# fmu-io.net
KiCad netlist of a schematic drawn in Altium Designer
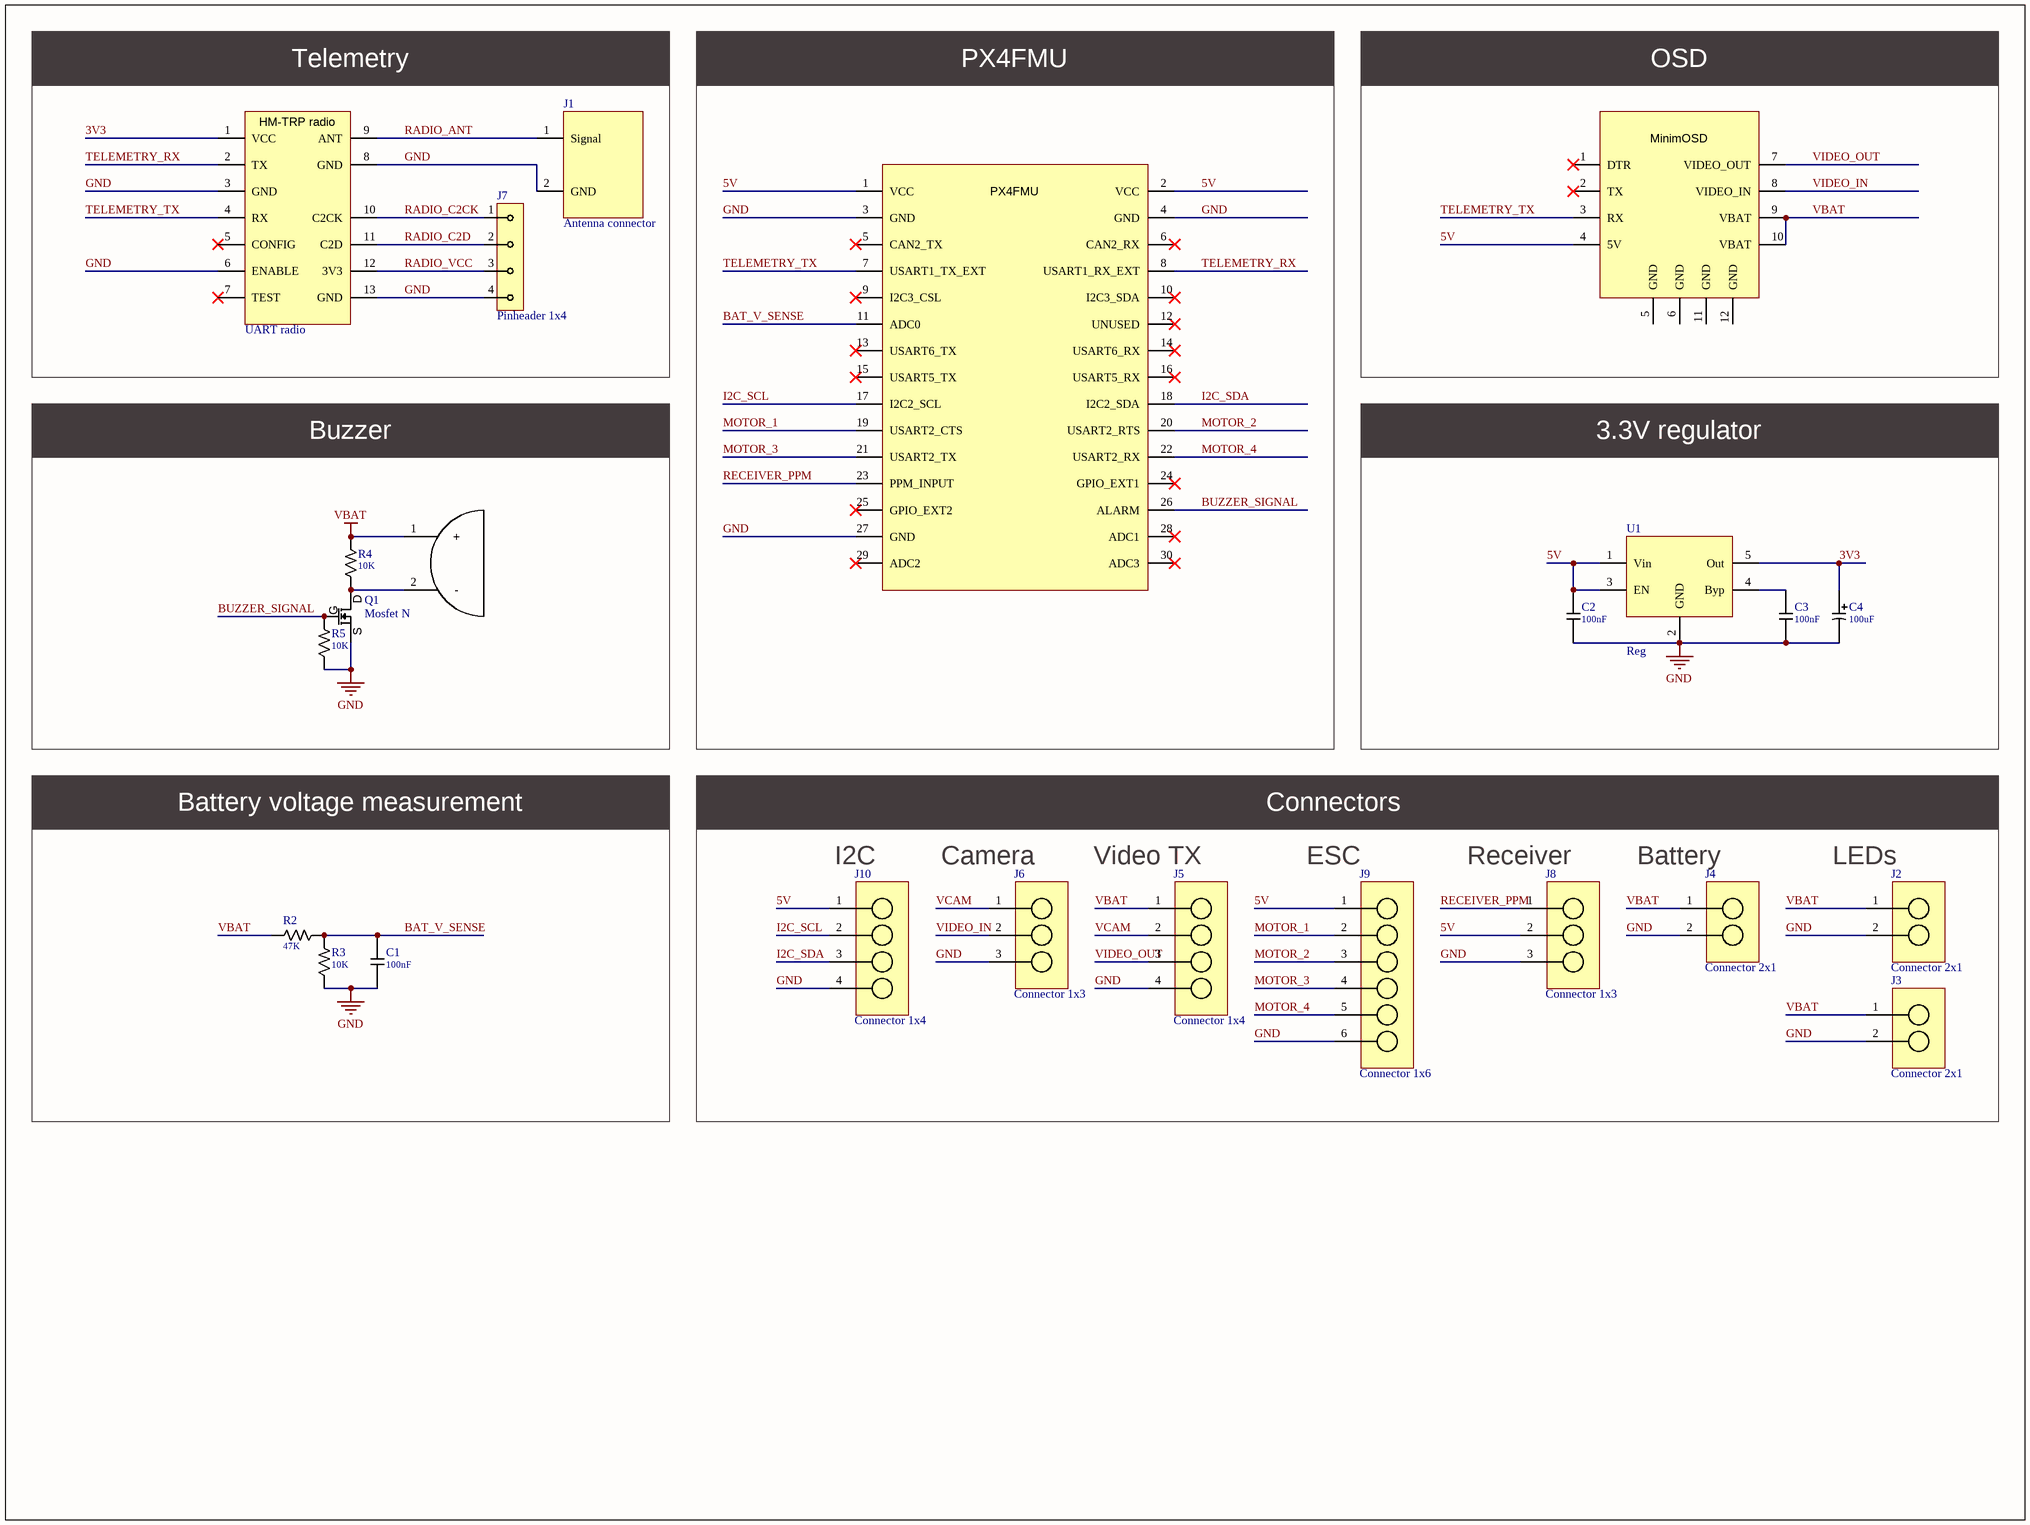
[diagram p0: fmu-io.SchDoc]

(export (version "E")
  (design (tool "Eeschema 10.0.6"))
  (components
    (comp (ref "C1")
      (value "100nF")
      (footprint "CAP-0603-GEN")
      (description "Capacitor")
      (fields (field (name "Comment") "CAPACITOR"))
      (libsource (lib "schematic-library") (part "CAPACITOR"))
    )
    (comp (ref "C2")
      (value "100nF")
      (footprint "CAP-0603-GEN")
      (description "Capacitor")
      (fields (field (name "Comment") "CAPACITOR"))
      (libsource (lib "custom") (part "CAPACITOR"))
    )
    (comp (ref "C3")
      (value "100nF")
      (footprint "CAP-0603-GEN")
      (description "Capacitor")
      (fields (field (name "Comment") "CAPACITOR"))
      (libsource (lib "custom") (part "CAPACITOR"))
    )
    (comp (ref "C4")
      (value "100uF")
      (footprint "CAP-1206-POL")
      (description "Polarized capacitor")
      (fields (field (name "Comment") "CAPACITOR-POLARIZED"))
      (libsource (lib "custom") (part "CAPACITOR-POLARIZED"))
    )
    (comp (ref "J1")
      (value "Antenna connector")
      (footprint "ANTENNA-CONNECTOR")
      (libsource (lib "schematic-library") (part "ANTENNA-CONNECTOR"))
    )
    (comp (ref "J2")
      (value "Connector 2x1")
      (footprint "DF13-2H-SMD")
      (description "Single row two contact connector")
      (libsource (lib "schematic-library") (part "CONNECTOR-1x2"))
    )
    (comp (ref "J3")
      (value "Connector 2x1")
      (footprint "DF13-2H-SMD")
      (description "Single row two contact connector")
      (libsource (lib "schematic-library") (part "CONNECTOR-1x2"))
    )
    (comp (ref "J4")
      (value "Connector 2x1")
      (footprint "JST-PA-2H-SMD")
      (description "Single row two contact connector")
      (libsource (lib "schematic-library") (part "CONNECTOR-1x2"))
    )
    (comp (ref "J5")
      (value "Connector 1x4")
      (footprint "DF13-4H-SMD")
      (description "Single row 4 contact connector")
      (libsource (lib "schematic-library") (part "CONNECTOR-1x4"))
    )
    (comp (ref "J6")
      (value "Connector 1x3")
      (footprint "DF13-3H-SMD")
      (description "Single row 3 contact connector")
      (libsource (lib "schematic-library") (part "CONNECTOR-1x3"))
    )
    (comp (ref "J7")
      (value "Pinheader 1x4")
      (footprint "PINHEADER-1x4-right-angle")
      (description "Single row four pin header")
      (libsource (lib "schematic-library") (part "PINHEADER-1x4"))
    )
    (comp (ref "J8")
      (value "Connector 1x3")
      (footprint "DF13-3H-SMD")
      (description "Single row 3 contact connector")
      (libsource (lib "schematic-library") (part "CONNECTOR-1x3"))
    )
    (comp (ref "J9")
      (value "Connector 1x6")
      (footprint "DF13-6H-SMD")
      (description "Single row 6 contact connector")
      (libsource (lib "schematic-library") (part "CONNECTOR-1x6"))
    )
    (comp (ref "J10")
      (value "Connector 1x4")
      (footprint "DF13-4H-SMD")
      (description "Single row 4 contact connector")
      (libsource (lib "schematic-library") (part "CONNECTOR-1x4"))
    )
    (comp (ref "OSD")
      (value "OSD")
      (footprint "MINIMOSD")
      (description "On-screen display")
      (libsource (lib "schematic-library") (part "MINIMOSD"))
    )
    (comp (ref "PX4FMU")
      (value "PX4FMU")
      (footprint "HEADER-2x15-SMD")
      (description "PX4FMU flight controller")
      (libsource (lib "schematic-library") (part "PX4FMU"))
    )
    (comp (ref "Q1")
      (value "Mosfet N")
      (footprint "SOT23-3")
      (description "N-channel mosfet")
      (libsource (lib "schematic-library") (part "MOSFET-N"))
    )
    (comp (ref "R1")
      (value "UART radio")
      (footprint "HM-TRP")
      (description "UART long range radio")
      (libsource (lib "schematic-library") (part "HM-TRP"))
    )
    (comp (ref "R2")
      (value "47K")
      (footprint "RESISTOR-0603")
      (description "Resistor")
      (fields (field (name "Comment") "RESISTOR"))
      (libsource (lib "schematic-library") (part "RESISTOR"))
    )
    (comp (ref "R3")
      (value "10K")
      (footprint "RESISTOR-0603")
      (description "Resistor")
      (fields (field (name "Comment") "RESISTOR"))
      (libsource (lib "schematic-library") (part "RESISTOR"))
    )
    (comp (ref "R4")
      (value "10K")
      (footprint "RESISTOR-0603")
      (description "Resistor")
      (fields (field (name "Comment") "RESISTOR"))
      (libsource (lib "schematic-library") (part "RESISTOR"))
    )
    (comp (ref "R5")
      (value "10K")
      (footprint "RESISTOR-0603")
      (description "Resistor")
      (fields (field (name "Comment") "RESISTOR"))
      (libsource (lib "schematic-library") (part "RESISTOR"))
    )
    (comp (ref "SG1")
      (value "Buzzer")
      (footprint "BUZZER-ABI-017-RC")
      (libsource (lib "schematic-library") (part "BUZZER"))
    )
    (comp (ref "U1")
      (value "Reg")
      (footprint "SOT23-5")
      (description "Voltage regulator")
      (libsource (lib "custom") (part "SOT23-REG"))
    )
  )
  (nets
    (net (code "1") (name "/3V3") (class "Default")
      (node (ref "C4") (pin "1") (pinfunction "1_1") (pintype "passive"))
      (node (ref "R1") (pin "1") (pinfunction "VCC_1") (pintype "passive"))
      (node (ref "U1") (pin "5") (pinfunction "Out_5") (pintype "passive"))
    )
    (net (code "2") (name "/5V") (class "Default")
      (node (ref "C2") (pin "2") (pinfunction "2_2") (pintype "passive"))
      (node (ref "J10") (pin "1") (pinfunction "1_1") (pintype "passive"))
      (node (ref "J8") (pin "2") (pinfunction "2_2") (pintype "passive"))
      (node (ref "J9") (pin "1") (pinfunction "1_1") (pintype "passive"))
      (node (ref "OSD") (pin "4") (pinfunction "5V_4") (pintype "passive"))
      (node (ref "PX4FMU") (pin "1") (pinfunction "VCC_1") (pintype "passive"))
      (node (ref "PX4FMU") (pin "2") (pinfunction "VCC_2") (pintype "passive"))
      (node (ref "U1") (pin "1") (pinfunction "Vin_1") (pintype "passive"))
      (node (ref "U1") (pin "3") (pinfunction "EN_3") (pintype "passive"))
    )
    (net (code "3") (name "/BAT_V_SENSE") (class "Default")
      (node (ref "C1") (pin "2") (pinfunction "2_2") (pintype "passive"))
      (node (ref "PX4FMU") (pin "11") (pinfunction "ADC0_11") (pintype "passive"))
      (node (ref "R2") (pin "2") (pinfunction "2_2") (pintype "passive"))
      (node (ref "R3") (pin "2") (pinfunction "2_2") (pintype "passive"))
    )
    (net (code "4") (name "/BUZZER_SIGNAL") (class "Default")
      (node (ref "PX4FMU") (pin "26") (pinfunction "ALARM_26") (pintype "passive"))
      (node (ref "Q1") (pin "1") (pinfunction "Gate_1") (pintype "passive"))
      (node (ref "R5") (pin "2") (pinfunction "2_2") (pintype "passive"))
    )
    (net (code "5") (name "/I2C_SCL") (class "Default")
      (node (ref "J10") (pin "2") (pinfunction "2_2") (pintype "passive"))
      (node (ref "PX4FMU") (pin "17") (pinfunction "I2C2_SCL_17") (pintype "passive"))
    )
    (net (code "6") (name "/I2C_SDA") (class "Default")
      (node (ref "J10") (pin "3") (pinfunction "3_3") (pintype "passive"))
      (node (ref "PX4FMU") (pin "18") (pinfunction "I2C2_SDA_18") (pintype "passive"))
    )
    (net (code "7") (name "/MOTOR_1") (class "Default")
      (node (ref "J9") (pin "2") (pinfunction "2_2") (pintype "passive"))
      (node (ref "PX4FMU") (pin "19") (pinfunction "USART2_CTS_19") (pintype "passive"))
    )
    (net (code "8") (name "/MOTOR_2") (class "Default")
      (node (ref "J9") (pin "3") (pinfunction "3_3") (pintype "passive"))
      (node (ref "PX4FMU") (pin "20") (pinfunction "USART2_RTS_20") (pintype "passive"))
    )
    (net (code "9") (name "/MOTOR_3") (class "Default")
      (node (ref "J9") (pin "4") (pinfunction "4_4") (pintype "passive"))
      (node (ref "PX4FMU") (pin "21") (pinfunction "USART2_TX_21") (pintype "passive"))
    )
    (net (code "10") (name "/MOTOR_4") (class "Default")
      (node (ref "J9") (pin "5") (pinfunction "5_5") (pintype "passive"))
      (node (ref "PX4FMU") (pin "22") (pinfunction "USART2_RX_22") (pintype "passive"))
    )
    (net (code "11") (name "/RADIO_ANT") (class "Default")
      (node (ref "J1") (pin "1") (pinfunction "Signal_1") (pintype "passive"))
      (node (ref "R1") (pin "9") (pinfunction "ANT_9") (pintype "passive"))
    )
    (net (code "12") (name "/RADIO_C2CK") (class "Default")
      (node (ref "J7") (pin "1") (pinfunction "1_1") (pintype "passive"))
      (node (ref "R1") (pin "10") (pinfunction "C2CK_10") (pintype "passive"))
    )
    (net (code "13") (name "/RADIO_C2D") (class "Default")
      (node (ref "J7") (pin "2") (pinfunction "2_2") (pintype "passive"))
      (node (ref "R1") (pin "11") (pinfunction "C2D_11") (pintype "passive"))
    )
    (net (code "14") (name "/RADIO_VCC") (class "Default")
      (node (ref "J7") (pin "3") (pinfunction "3_3") (pintype "passive"))
      (node (ref "R1") (pin "12") (pinfunction "3V3_12") (pintype "passive"))
    )
    (net (code "15") (name "/RECEIVER_PPM") (class "Default")
      (node (ref "J8") (pin "1") (pinfunction "1_1") (pintype "passive"))
      (node (ref "PX4FMU") (pin "23") (pinfunction "PPM_INPUT_23") (pintype "passive"))
    )
    (net (code "16") (name "/TELEMETRY_RX") (class "Default")
      (node (ref "PX4FMU") (pin "8") (pinfunction "USART1_RX_EXT_8") (pintype "passive"))
      (node (ref "R1") (pin "2") (pinfunction "TX_2") (pintype "passive"))
    )
    (net (code "17") (name "/TELEMETRY_TX") (class "Default")
      (node (ref "OSD") (pin "3") (pinfunction "RX_3") (pintype "passive"))
      (node (ref "PX4FMU") (pin "7") (pinfunction "USART1_TX_EXT_7") (pintype "passive"))
      (node (ref "R1") (pin "4") (pinfunction "RX_4") (pintype "passive"))
    )
    (net (code "18") (name "/VCAM") (class "Default")
      (node (ref "J5") (pin "2") (pinfunction "2_2") (pintype "passive"))
      (node (ref "J6") (pin "1") (pinfunction "1_1") (pintype "passive"))
    )
    (net (code "19") (name "/VIDEO_IN") (class "Default")
      (node (ref "J6") (pin "2") (pinfunction "2_2") (pintype "passive"))
      (node (ref "OSD") (pin "8") (pinfunction "VIDEO_IN_8") (pintype "passive"))
    )
    (net (code "20") (name "/VIDEO_OUT") (class "Default")
      (node (ref "J5") (pin "3") (pinfunction "3_3") (pintype "passive"))
      (node (ref "OSD") (pin "7") (pinfunction "VIDEO_OUT_7") (pintype "passive"))
    )
    (net (code "21") (name "GND") (class "Default")
      (node (ref "C1") (pin "1") (pinfunction "1_1") (pintype "passive"))
      (node (ref "C2") (pin "1") (pinfunction "1_1") (pintype "passive"))
      (node (ref "C3") (pin "1") (pinfunction "1_1") (pintype "passive"))
      (node (ref "C4") (pin "2") (pinfunction "2_2") (pintype "passive"))
      (node (ref "J1") (pin "2") (pinfunction "GND_2") (pintype "passive"))
      (node (ref "J10") (pin "4") (pinfunction "4_4") (pintype "passive"))
      (node (ref "J2") (pin "2") (pinfunction "2_2") (pintype "passive"))
      (node (ref "J3") (pin "2") (pinfunction "2_2") (pintype "passive"))
      (node (ref "J4") (pin "2") (pinfunction "2_2") (pintype "passive"))
      (node (ref "J5") (pin "4") (pinfunction "4_4") (pintype "passive"))
      (node (ref "J6") (pin "3") (pinfunction "3_3") (pintype "passive"))
      (node (ref "J7") (pin "4") (pinfunction "4_4") (pintype "passive"))
      (node (ref "J8") (pin "3") (pinfunction "3_3") (pintype "passive"))
      (node (ref "J9") (pin "6") (pinfunction "6_6") (pintype "passive"))
      (node (ref "PX4FMU") (pin "27") (pinfunction "GND_27") (pintype "passive"))
      (node (ref "PX4FMU") (pin "3") (pinfunction "GND_3") (pintype "passive"))
      (node (ref "PX4FMU") (pin "4") (pinfunction "GND_4") (pintype "passive"))
      (node (ref "Q1") (pin "2") (pinfunction "Source_2") (pintype "passive"))
      (node (ref "R1") (pin "13") (pinfunction "GND_13") (pintype "passive"))
      (node (ref "R1") (pin "3") (pinfunction "GND_3") (pintype "passive"))
      (node (ref "R1") (pin "6") (pinfunction "ENABLE_6") (pintype "passive"))
      (node (ref "R1") (pin "8") (pinfunction "GND_8") (pintype "passive"))
      (node (ref "R3") (pin "1") (pinfunction "1_1") (pintype "passive"))
      (node (ref "R5") (pin "1") (pinfunction "1_1") (pintype "passive"))
      (node (ref "U1") (pin "2") (pinfunction "GND_2") (pintype "passive"))
    )
    (net (code "22") (name "Net-(Q1-Drain)") (class "Default")
      (node (ref "Q1") (pin "3") (pinfunction "Drain_3") (pintype "passive"))
      (node (ref "R4") (pin "1") (pinfunction "1_1") (pintype "passive"))
      (node (ref "SG1") (pin "2") (pinfunction "-_2") (pintype "passive"))
    )
    (net (code "23") (name "Net-(U1-Byp)") (class "Default")
      (node (ref "C3") (pin "2") (pinfunction "2_2") (pintype "passive"))
      (node (ref "U1") (pin "4") (pinfunction "Byp_4") (pintype "passive"))
    )
    (net (code "24") (name "VBAT") (class "Default")
      (node (ref "J2") (pin "1") (pinfunction "1_1") (pintype "passive"))
      (node (ref "J3") (pin "1") (pinfunction "1_1") (pintype "passive"))
      (node (ref "J4") (pin "1") (pinfunction "1_1") (pintype "passive"))
      (node (ref "J5") (pin "1") (pinfunction "1_1") (pintype "passive"))
      (node (ref "OSD") (pin "10") (pinfunction "VBAT_10") (pintype "passive"))
      (node (ref "OSD") (pin "9") (pinfunction "VBAT_9") (pintype "passive"))
      (node (ref "R2") (pin "1") (pinfunction "1_1") (pintype "passive"))
      (node (ref "R4") (pin "2") (pinfunction "2_2") (pintype "passive"))
      (node (ref "SG1") (pin "1") (pinfunction "+_1") (pintype "passive"))
    )
    (net (code "25") (name "unconnected-(OSD-DTR-Pad1)") (class "Default")
      (node (ref "OSD") (pin "1") (pinfunction "DTR_1") (pintype "passive+no_connect"))
    )
    (net (code "26") (name "unconnected-(OSD-GND-Pad5)") (class "Default")
      (node (ref "OSD") (pin "5") (pinfunction "GND_5") (pintype "passive"))
    )
    (net (code "27") (name "unconnected-(OSD-GND-Pad6)") (class "Default")
      (node (ref "OSD") (pin "6") (pinfunction "GND_6") (pintype "passive"))
    )
    (net (code "28") (name "unconnected-(OSD-GND-Pad11)") (class "Default")
      (node (ref "OSD") (pin "11") (pinfunction "GND_11") (pintype "passive"))
    )
    (net (code "29") (name "unconnected-(OSD-GND-Pad12)") (class "Default")
      (node (ref "OSD") (pin "12") (pinfunction "GND_12") (pintype "passive"))
    )
    (net (code "30") (name "unconnected-(OSD-TX-Pad2)") (class "Default")
      (node (ref "OSD") (pin "2") (pinfunction "TX_2") (pintype "passive+no_connect"))
    )
    (net (code "31") (name "unconnected-(PX4FMU-ADC1-Pad28)") (class "Default")
      (node (ref "PX4FMU") (pin "28") (pinfunction "ADC1_28") (pintype "passive+no_connect"))
    )
    (net (code "32") (name "unconnected-(PX4FMU-ADC2-Pad29)") (class "Default")
      (node (ref "PX4FMU") (pin "29") (pinfunction "ADC2_29") (pintype "passive+no_connect"))
    )
    (net (code "33") (name "unconnected-(PX4FMU-ADC3-Pad30)") (class "Default")
      (node (ref "PX4FMU") (pin "30") (pinfunction "ADC3_30") (pintype "passive+no_connect"))
    )
    (net (code "34") (name "unconnected-(PX4FMU-CAN2_RX-Pad6)") (class "Default")
      (node (ref "PX4FMU") (pin "6") (pinfunction "CAN2_RX_6") (pintype "passive+no_connect"))
    )
    (net (code "35") (name "unconnected-(PX4FMU-CAN2_TX-Pad5)") (class "Default")
      (node (ref "PX4FMU") (pin "5") (pinfunction "CAN2_TX_5") (pintype "passive+no_connect"))
    )
    (net (code "36") (name "unconnected-(PX4FMU-GPIO_EXT1-Pad24)") (class "Default")
      (node (ref "PX4FMU") (pin "24") (pinfunction "GPIO_EXT1_24") (pintype "passive+no_connect"))
    )
    (net (code "37") (name "unconnected-(PX4FMU-GPIO_EXT2-Pad25)") (class "Default")
      (node (ref "PX4FMU") (pin "25") (pinfunction "GPIO_EXT2_25") (pintype "passive+no_connect"))
    )
    (net (code "38") (name "unconnected-(PX4FMU-I2C3_CSL-Pad9)") (class "Default")
      (node (ref "PX4FMU") (pin "9") (pinfunction "I2C3_CSL_9") (pintype "passive+no_connect"))
    )
    (net (code "39") (name "unconnected-(PX4FMU-I2C3_SDA-Pad10)") (class "Default")
      (node (ref "PX4FMU") (pin "10") (pinfunction "I2C3_SDA_10") (pintype "passive+no_connect"))
    )
    (net (code "40") (name "unconnected-(PX4FMU-UNUSED-Pad12)") (class "Default")
      (node (ref "PX4FMU") (pin "12") (pinfunction "UNUSED_12") (pintype "passive+no_connect"))
    )
    (net (code "41") (name "unconnected-(PX4FMU-USART5_RX-Pad16)") (class "Default")
      (node (ref "PX4FMU") (pin "16") (pinfunction "USART5_RX_16") (pintype "passive+no_connect"))
    )
    (net (code "42") (name "unconnected-(PX4FMU-USART5_TX-Pad15)") (class "Default")
      (node (ref "PX4FMU") (pin "15") (pinfunction "USART5_TX_15") (pintype "passive+no_connect"))
    )
    (net (code "43") (name "unconnected-(PX4FMU-USART6_RX-Pad14)") (class "Default")
      (node (ref "PX4FMU") (pin "14") (pinfunction "USART6_RX_14") (pintype "passive+no_connect"))
    )
    (net (code "44") (name "unconnected-(PX4FMU-USART6_TX-Pad13)") (class "Default")
      (node (ref "PX4FMU") (pin "13") (pinfunction "USART6_TX_13") (pintype "passive+no_connect"))
    )
    (net (code "45") (name "unconnected-(R1-CONFIG-Pad5)") (class "Default")
      (node (ref "R1") (pin "5") (pinfunction "CONFIG_5") (pintype "passive+no_connect"))
    )
    (net (code "46") (name "unconnected-(R1-TEST-Pad7)") (class "Default")
      (node (ref "R1") (pin "7") (pinfunction "TEST_7") (pintype "passive+no_connect"))
    )
  )
)
